# SINUX_F1_POWER.net
KiCad netlist of a schematic drawn in Altium Designer
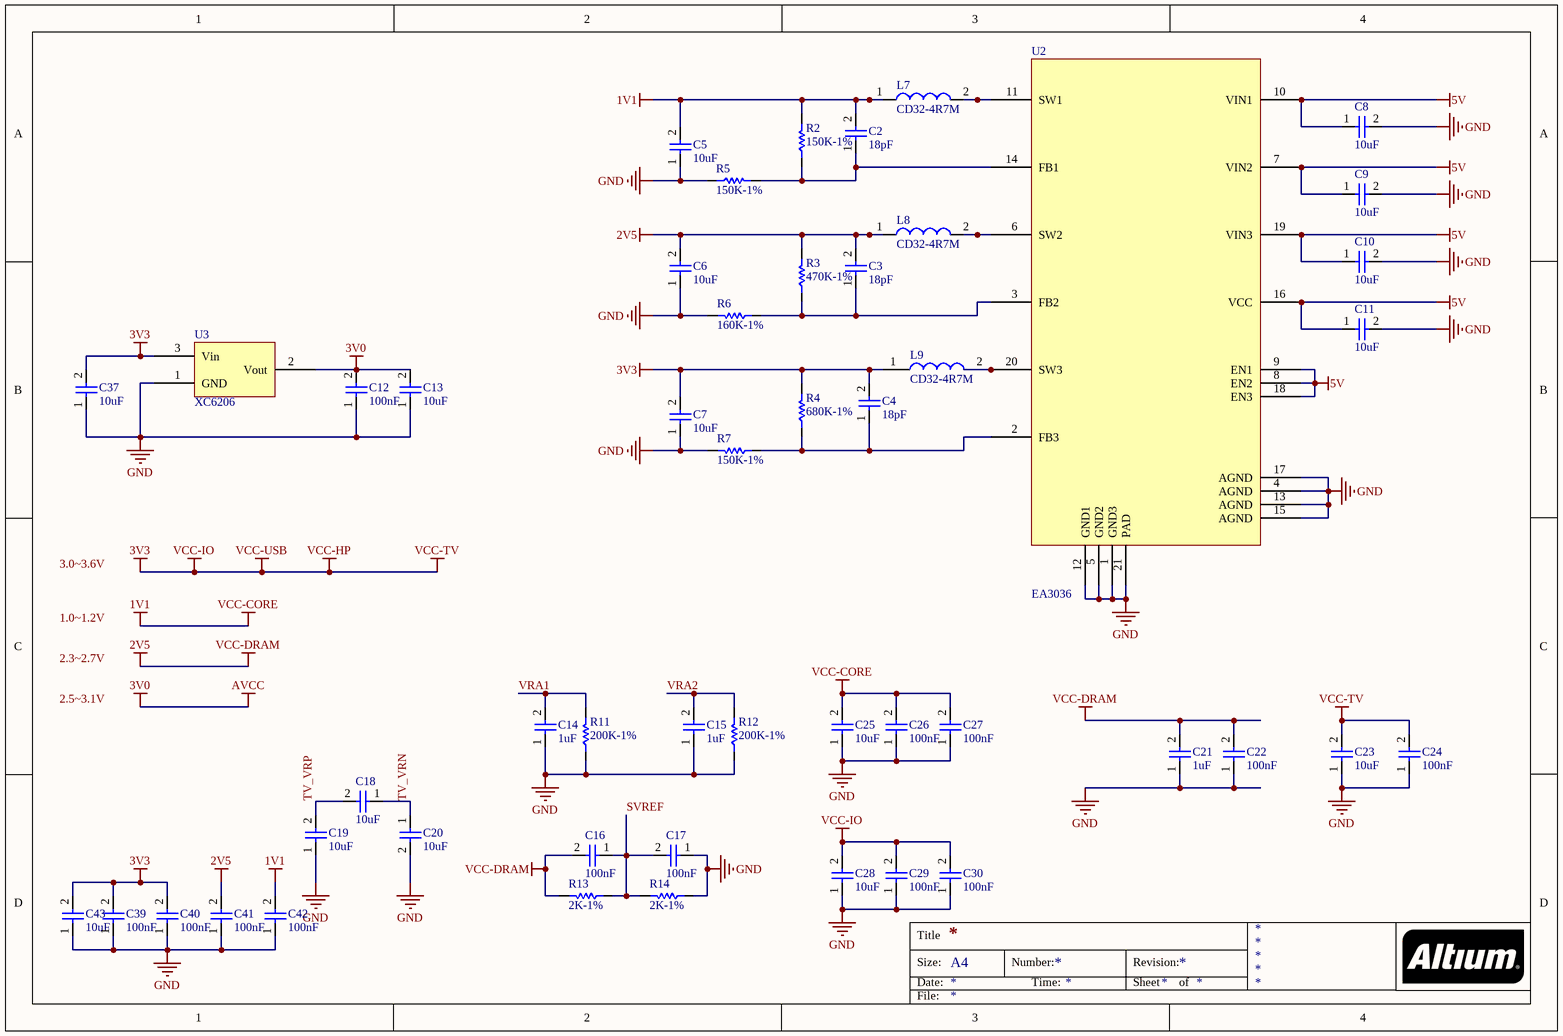
[diagram p0: SINUX_F1_POWER.SchDoc]

(export (version "E")
  (design (tool "Eeschema 10.0.6"))
  (components
    (comp (ref "C2") (value "18pF") (footprint "SMD 0805") (libsource (lib "3D LIB") (part "CAP NON")))
    (comp (ref "C3") (value "18pF") (footprint "SMD 0805") (libsource (lib "3D LIB") (part "CAP NON")))
    (comp (ref "C4") (value "18pF") (footprint "SMD 0805") (libsource (lib "3D LIB") (part "CAP NON")))
    (comp (ref "C5") (value "10uF") (footprint "SMD 0805") (libsource (lib "3D LIB") (part "CAP NON")))
    (comp (ref "C6") (value "10uF") (footprint "SMD 0805") (libsource (lib "3D LIB") (part "CAP NON")))
    (comp (ref "C7") (value "10uF") (footprint "SMD 0805") (libsource (lib "3D LIB") (part "CAP NON")))
    (comp (ref "C8") (value "10uF") (footprint "SMD 0805") (libsource (lib "3D LIB") (part "CAP NON")))
    (comp (ref "C9") (value "10uF") (footprint "SMD 0805") (libsource (lib "3D LIB") (part "CAP NON")))
    (comp (ref "C10") (value "10uF") (footprint "SMD 0805") (libsource (lib "3D LIB") (part "CAP NON")))
    (comp (ref "C11") (value "10uF") (footprint "SMD 0805") (libsource (lib "3D LIB") (part "CAP NON")))
    (comp (ref "C12") (value "100nF") (footprint "SMD 0805") (libsource (lib "3D LIB") (part "CAP NON")))
    (comp (ref "C13") (value "10uF") (footprint "SMD 0805") (libsource (lib "3D LIB") (part "CAP NON")))
    (comp (ref "C14") (value "1uF") (footprint "SMD 0805") (libsource (lib "3D LIB") (part "CAP NON")))
    (comp (ref "C15") (value "1uF") (footprint "SMD 0805") (libsource (lib "3D LIB") (part "CAP NON")))
    (comp (ref "C16") (value "100nF") (footprint "SMD 0805") (libsource (lib "3D LIB") (part "CAP NON")))
    (comp (ref "C17") (value "100nF") (footprint "SMD 0805") (libsource (lib "3D LIB") (part "CAP NON")))
    (comp (ref "C18") (value "10uF") (footprint "SMD 0805") (libsource (lib "3D LIB") (part "CAP NON")))
    (comp (ref "C19") (value "10uF") (footprint "SMD 0805") (libsource (lib "3D LIB") (part "CAP NON")))
    (comp (ref "C20") (value "10uF") (footprint "SMD 0805") (libsource (lib "3D LIB") (part "CAP NON")))
    (comp (ref "C21") (value "1uF") (footprint "SMD 0805") (libsource (lib "3D LIB") (part "CAP NON")))
    (comp (ref "C22") (value "100nF") (footprint "SMD 0805") (libsource (lib "3D LIB") (part "CAP NON")))
    (comp (ref "C23") (value "10uF") (footprint "SMD 0805") (libsource (lib "3D LIB") (part "CAP NON")))
    (comp (ref "C24") (value "100nF") (footprint "SMD 0805") (libsource (lib "3D LIB") (part "CAP NON")))
    (comp (ref "C25") (value "10uF") (footprint "SMD 0805") (libsource (lib "3D LIB") (part "CAP NON")))
    (comp (ref "C26") (value "100nF") (footprint "SMD 0805") (libsource (lib "3D LIB") (part "CAP NON")))
    (comp (ref "C27") (value "100nF") (footprint "SMD 0805") (libsource (lib "3D LIB") (part "CAP NON")))
    (comp (ref "C28") (value "10uF") (footprint "SMD 0805") (libsource (lib "3D LIB") (part "CAP NON")))
    (comp (ref "C29") (value "100nF") (footprint "SMD 0805") (libsource (lib "3D LIB") (part "CAP NON")))
    (comp (ref "C30") (value "100nF") (footprint "SMD 0805") (libsource (lib "3D LIB") (part "CAP NON")))
    (comp (ref "C37") (value "10uF") (footprint "SMD 0805") (libsource (lib "3D LIB") (part "CAP NON")))
    (comp (ref "C39") (value "100nF") (footprint "SMD 0805") (libsource (lib "3D LIB") (part "CAP NON")))
    (comp (ref "C40") (value "100nF") (footprint "SMD 0805") (libsource (lib "3D LIB") (part "CAP NON")))
    (comp (ref "C41") (value "100nF") (footprint "SMD 0805") (libsource (lib "3D LIB") (part "CAP NON")))
    (comp (ref "C42") (value "100nF") (footprint "SMD 0805") (libsource (lib "3D LIB") (part "CAP NON")))
    (comp (ref "C43") (value "10uF") (footprint "SMD 0805") (libsource (lib "3D LIB") (part "CAP NON")))
    (comp (ref "L7")
      (value "CD32-4R7M")
      (footprint "SamacSys:CD324R7M")
      (description "Inductor")
      (libsource (lib "SamacSys") (part "CD32-4R7M"))
    )
    (comp (ref "L8")
      (value "CD32-4R7M")
      (footprint "SamacSys:CD324R7M")
      (description "Inductor")
      (libsource (lib "SamacSys") (part "CD32-4R7M"))
    )
    (comp (ref "L9")
      (value "CD32-4R7M")
      (footprint "SamacSys:CD324R7M")
      (description "Inductor")
      (libsource (lib "SamacSys") (part "CD32-4R7M"))
    )
    (comp (ref "R2") (value "150K-1%") (footprint "0805_1/8W") (libsource (lib "3D LIB") (part "RESISTOR")))
    (comp (ref "R3") (value "470K-1%") (footprint "0805_1/8W") (libsource (lib "3D LIB") (part "RESISTOR")))
    (comp (ref "R4") (value "680K-1%") (footprint "0805_1/8W") (libsource (lib "3D LIB") (part "RESISTOR")))
    (comp (ref "R5") (value "150K-1%") (footprint "0805_1/8W") (libsource (lib "3D LIB") (part "RESISTOR")))
    (comp (ref "R6") (value "160K-1%") (footprint "0805_1/8W") (libsource (lib "3D LIB") (part "RESISTOR")))
    (comp (ref "R7") (value "150K-1%") (footprint "0805_1/8W") (libsource (lib "3D LIB") (part "RESISTOR")))
    (comp (ref "R11") (value "200K-1%") (footprint "0805_1/8W") (libsource (lib "3D LIB") (part "RESISTOR")))
    (comp (ref "R12") (value "200K-1%") (footprint "0805_1/8W") (libsource (lib "3D LIB") (part "RESISTOR")))
    (comp (ref "R13") (value "2K-1%") (footprint "0805_1/8W") (libsource (lib "3D LIB") (part "RESISTOR")))
    (comp (ref "R14") (value "2K-1%") (footprint "0805_1/8W") (libsource (lib "3D LIB") (part "RESISTOR")))
    (comp (ref "U2")
      (value "EA3036")
      (footprint "QFN40P300X300X80-21N")
      (libsource (lib "EA3036") (part "EA3036"))
    )
    (comp (ref "U3")
      (value "XC6206")
      (footprint "SOT95P280X130-3N")
      (libsource (lib "xc6206") (part "XC6206"))
    )
  )
  (nets
    (net (code "5") (name "/SVREF") (class "Default")
      (node (ref "C16") (pin "1") (pinfunction "1_1") (pintype "passive"))
      (node (ref "C17") (pin "2") (pinfunction "2_2") (pintype "passive"))
      (node (ref "R13") (pin "1") (pinfunction "1_1") (pintype "passive"))
      (node (ref "R14") (pin "2") (pinfunction "2_2") (pintype "passive"))
    )
    (net (code "6") (name "/TV_VRN") (class "Default")
      (node (ref "C18") (pin "1") (pinfunction "1_1") (pintype "passive"))
      (node (ref "C20") (pin "1") (pinfunction "1_1") (pintype "passive"))
    )
    (net (code "7") (name "/TV_VRP") (class "Default")
      (node (ref "C18") (pin "2") (pinfunction "2_2") (pintype "passive"))
      (node (ref "C19") (pin "2") (pinfunction "2_2") (pintype "passive"))
    )
    (net (code "8") (name "/VRA1") (class "Default")
      (node (ref "C14") (pin "2") (pinfunction "2_2") (pintype "passive"))
      (node (ref "R11") (pin "2") (pinfunction "2_2") (pintype "passive"))
    )
    (net (code "9") (name "/VRA2") (class "Default")
      (node (ref "C15") (pin "2") (pinfunction "2_2") (pintype "passive"))
      (node (ref "R12") (pin "2") (pinfunction "2_2") (pintype "passive"))
    )
    (net (code "10") (name "1V1") (class "Default")
      (node (ref "C2") (pin "2") (pinfunction "2_2") (pintype "passive"))
      (node (ref "C25") (pin "2") (pinfunction "2_2") (pintype "passive"))
      (node (ref "C26") (pin "2") (pinfunction "2_2") (pintype "passive"))
      (node (ref "C27") (pin "2") (pinfunction "2_2") (pintype "passive"))
      (node (ref "C42") (pin "2") (pinfunction "2_2") (pintype "passive"))
      (node (ref "C5") (pin "2") (pinfunction "2_2") (pintype "passive"))
      (node (ref "L7") (pin "1") (pinfunction "1_1") (pintype "passive"))
      (node (ref "R2") (pin "2") (pinfunction "2_2") (pintype "passive"))
    )
    (net (code "11") (name "2V5") (class "Default")
      (node (ref "C16") (pin "2") (pinfunction "2_2") (pintype "passive"))
      (node (ref "C21") (pin "2") (pinfunction "2_2") (pintype "passive"))
      (node (ref "C22") (pin "2") (pinfunction "2_2") (pintype "passive"))
      (node (ref "C3") (pin "2") (pinfunction "2_2") (pintype "passive"))
      (node (ref "C41") (pin "2") (pinfunction "2_2") (pintype "passive"))
      (node (ref "C6") (pin "2") (pinfunction "2_2") (pintype "passive"))
      (node (ref "L8") (pin "1") (pinfunction "1_1") (pintype "passive"))
      (node (ref "R13") (pin "2") (pinfunction "2_2") (pintype "passive"))
      (node (ref "R3") (pin "2") (pinfunction "2_2") (pintype "passive"))
    )
    (net (code "12") (name "3V0") (class "Default")
      (node (ref "C12") (pin "2") (pinfunction "2_2") (pintype "passive"))
      (node (ref "C13") (pin "2") (pinfunction "2_2") (pintype "passive"))
      (node (ref "U3") (pin "2") (pinfunction "Vout_2") (pintype "passive"))
    )
    (net (code "13") (name "3V3") (class "Default")
      (node (ref "C23") (pin "2") (pinfunction "2_2") (pintype "passive"))
      (node (ref "C24") (pin "2") (pinfunction "2_2") (pintype "passive"))
      (node (ref "C28") (pin "2") (pinfunction "2_2") (pintype "passive"))
      (node (ref "C29") (pin "2") (pinfunction "2_2") (pintype "passive"))
      (node (ref "C30") (pin "2") (pinfunction "2_2") (pintype "passive"))
      (node (ref "C37") (pin "2") (pinfunction "2_2") (pintype "passive"))
      (node (ref "C39") (pin "2") (pinfunction "2_2") (pintype "passive"))
      (node (ref "C4") (pin "2") (pinfunction "2_2") (pintype "passive"))
      (node (ref "C40") (pin "2") (pinfunction "2_2") (pintype "passive"))
      (node (ref "C43") (pin "2") (pinfunction "2_2") (pintype "passive"))
      (node (ref "C7") (pin "2") (pinfunction "2_2") (pintype "passive"))
      (node (ref "L9") (pin "1") (pinfunction "1_1") (pintype "passive"))
      (node (ref "R4") (pin "2") (pinfunction "2_2") (pintype "passive"))
      (node (ref "U3") (pin "3") (pinfunction "Vin_3") (pintype "passive"))
    )
    (net (code "14") (name "5V") (class "Default")
      (node (ref "C10") (pin "1") (pinfunction "1_1") (pintype "passive"))
      (node (ref "C11") (pin "1") (pinfunction "1_1") (pintype "passive"))
      (node (ref "C8") (pin "1") (pinfunction "1_1") (pintype "passive"))
      (node (ref "C9") (pin "1") (pinfunction "1_1") (pintype "passive"))
      (node (ref "U2") (pin "10") (pinfunction "VIN1_10") (pintype "passive"))
      (node (ref "U2") (pin "16") (pinfunction "VCC_16") (pintype "passive"))
      (node (ref "U2") (pin "18") (pinfunction "EN3_18") (pintype "passive"))
      (node (ref "U2") (pin "19") (pinfunction "VIN3_19") (pintype "passive"))
      (node (ref "U2") (pin "7") (pinfunction "VIN2_7") (pintype "passive"))
      (node (ref "U2") (pin "8") (pinfunction "EN2_8") (pintype "passive"))
      (node (ref "U2") (pin "9") (pinfunction "EN1_9") (pintype "passive"))
    )
    (net (code "15") (name "GND") (class "Default")
      (node (ref "C10") (pin "2") (pinfunction "2_2") (pintype "passive"))
      (node (ref "C11") (pin "2") (pinfunction "2_2") (pintype "passive"))
      (node (ref "C12") (pin "1") (pinfunction "1_1") (pintype "passive"))
      (node (ref "C13") (pin "1") (pinfunction "1_1") (pintype "passive"))
      (node (ref "C14") (pin "1") (pinfunction "1_1") (pintype "passive"))
      (node (ref "C15") (pin "1") (pinfunction "1_1") (pintype "passive"))
      (node (ref "C17") (pin "1") (pinfunction "1_1") (pintype "passive"))
      (node (ref "C19") (pin "1") (pinfunction "1_1") (pintype "passive"))
      (node (ref "C20") (pin "2") (pinfunction "2_2") (pintype "passive"))
      (node (ref "C21") (pin "1") (pinfunction "1_1") (pintype "passive"))
      (node (ref "C22") (pin "1") (pinfunction "1_1") (pintype "passive"))
      (node (ref "C23") (pin "1") (pinfunction "1_1") (pintype "passive"))
      (node (ref "C24") (pin "1") (pinfunction "1_1") (pintype "passive"))
      (node (ref "C25") (pin "1") (pinfunction "1_1") (pintype "passive"))
      (node (ref "C26") (pin "1") (pinfunction "1_1") (pintype "passive"))
      (node (ref "C27") (pin "1") (pinfunction "1_1") (pintype "passive"))
      (node (ref "C28") (pin "1") (pinfunction "1_1") (pintype "passive"))
      (node (ref "C29") (pin "1") (pinfunction "1_1") (pintype "passive"))
      (node (ref "C30") (pin "1") (pinfunction "1_1") (pintype "passive"))
      (node (ref "C37") (pin "1") (pinfunction "1_1") (pintype "passive"))
      (node (ref "C39") (pin "1") (pinfunction "1_1") (pintype "passive"))
      (node (ref "C40") (pin "1") (pinfunction "1_1") (pintype "passive"))
      (node (ref "C41") (pin "1") (pinfunction "1_1") (pintype "passive"))
      (node (ref "C42") (pin "1") (pinfunction "1_1") (pintype "passive"))
      (node (ref "C43") (pin "1") (pinfunction "1_1") (pintype "passive"))
      (node (ref "C5") (pin "1") (pinfunction "1_1") (pintype "passive"))
      (node (ref "C6") (pin "1") (pinfunction "1_1") (pintype "passive"))
      (node (ref "C7") (pin "1") (pinfunction "1_1") (pintype "passive"))
      (node (ref "C8") (pin "2") (pinfunction "2_2") (pintype "passive"))
      (node (ref "C9") (pin "2") (pinfunction "2_2") (pintype "passive"))
      (node (ref "R11") (pin "1") (pinfunction "1_1") (pintype "passive"))
      (node (ref "R12") (pin "1") (pinfunction "1_1") (pintype "passive"))
      (node (ref "R14") (pin "1") (pinfunction "1_1") (pintype "passive"))
      (node (ref "R5") (pin "1") (pinfunction "1_1") (pintype "passive"))
      (node (ref "R6") (pin "2") (pinfunction "2_2") (pintype "passive"))
      (node (ref "R7") (pin "2") (pinfunction "2_2") (pintype "passive"))
      (node (ref "U2") (pin "1") (pinfunction "GND3_1") (pintype "passive"))
      (node (ref "U2") (pin "12") (pinfunction "GND1_12") (pintype "passive"))
      (node (ref "U2") (pin "13") (pinfunction "AGND_13") (pintype "passive"))
      (node (ref "U2") (pin "15") (pinfunction "AGND_15") (pintype "passive"))
      (node (ref "U2") (pin "17") (pinfunction "AGND_17") (pintype "passive"))
      (node (ref "U2") (pin "21") (pinfunction "PAD_21") (pintype "passive"))
      (node (ref "U2") (pin "4") (pinfunction "AGND_4") (pintype "passive"))
      (node (ref "U2") (pin "5") (pinfunction "GND2_5") (pintype "passive"))
      (node (ref "U3") (pin "1") (pinfunction "GND_1") (pintype "passive"))
    )
    (net (code "16") (name "Net-(U2-FB1)") (class "Default")
      (node (ref "C2") (pin "1") (pinfunction "1_1") (pintype "passive"))
      (node (ref "R2") (pin "1") (pinfunction "1_1") (pintype "passive"))
      (node (ref "R5") (pin "2") (pinfunction "2_2") (pintype "passive"))
      (node (ref "U2") (pin "14") (pinfunction "FB1_14") (pintype "passive"))
    )
    (net (code "17") (name "Net-(U2-FB2)") (class "Default")
      (node (ref "C3") (pin "1") (pinfunction "1_1") (pintype "passive"))
      (node (ref "R3") (pin "1") (pinfunction "1_1") (pintype "passive"))
      (node (ref "R6") (pin "1") (pinfunction "1_1") (pintype "passive"))
      (node (ref "U2") (pin "3") (pinfunction "FB2_3") (pintype "passive"))
    )
    (net (code "18") (name "Net-(U2-FB3)") (class "Default")
      (node (ref "C4") (pin "1") (pinfunction "1_1") (pintype "passive"))
      (node (ref "R4") (pin "1") (pinfunction "1_1") (pintype "passive"))
      (node (ref "R7") (pin "1") (pinfunction "1_1") (pintype "passive"))
      (node (ref "U2") (pin "2") (pinfunction "FB3_2") (pintype "passive"))
    )
    (net (code "19") (name "Net-(U2-SW1)") (class "Default")
      (node (ref "L7") (pin "2") (pinfunction "2_2") (pintype "passive"))
      (node (ref "U2") (pin "11") (pinfunction "SW1_11") (pintype "passive"))
    )
    (net (code "20") (name "Net-(U2-SW2)") (class "Default")
      (node (ref "L8") (pin "2") (pinfunction "2_2") (pintype "passive"))
      (node (ref "U2") (pin "6") (pinfunction "SW2_6") (pintype "passive"))
    )
    (net (code "21") (name "Net-(U2-SW3)") (class "Default")
      (node (ref "L9") (pin "2") (pinfunction "2_2") (pintype "passive"))
      (node (ref "U2") (pin "20") (pinfunction "SW3_20") (pintype "passive"))
    )
  )
)
